# PwrGenBrd_v4_2.net
KiCad netlist of a schematic drawn in EAGLE
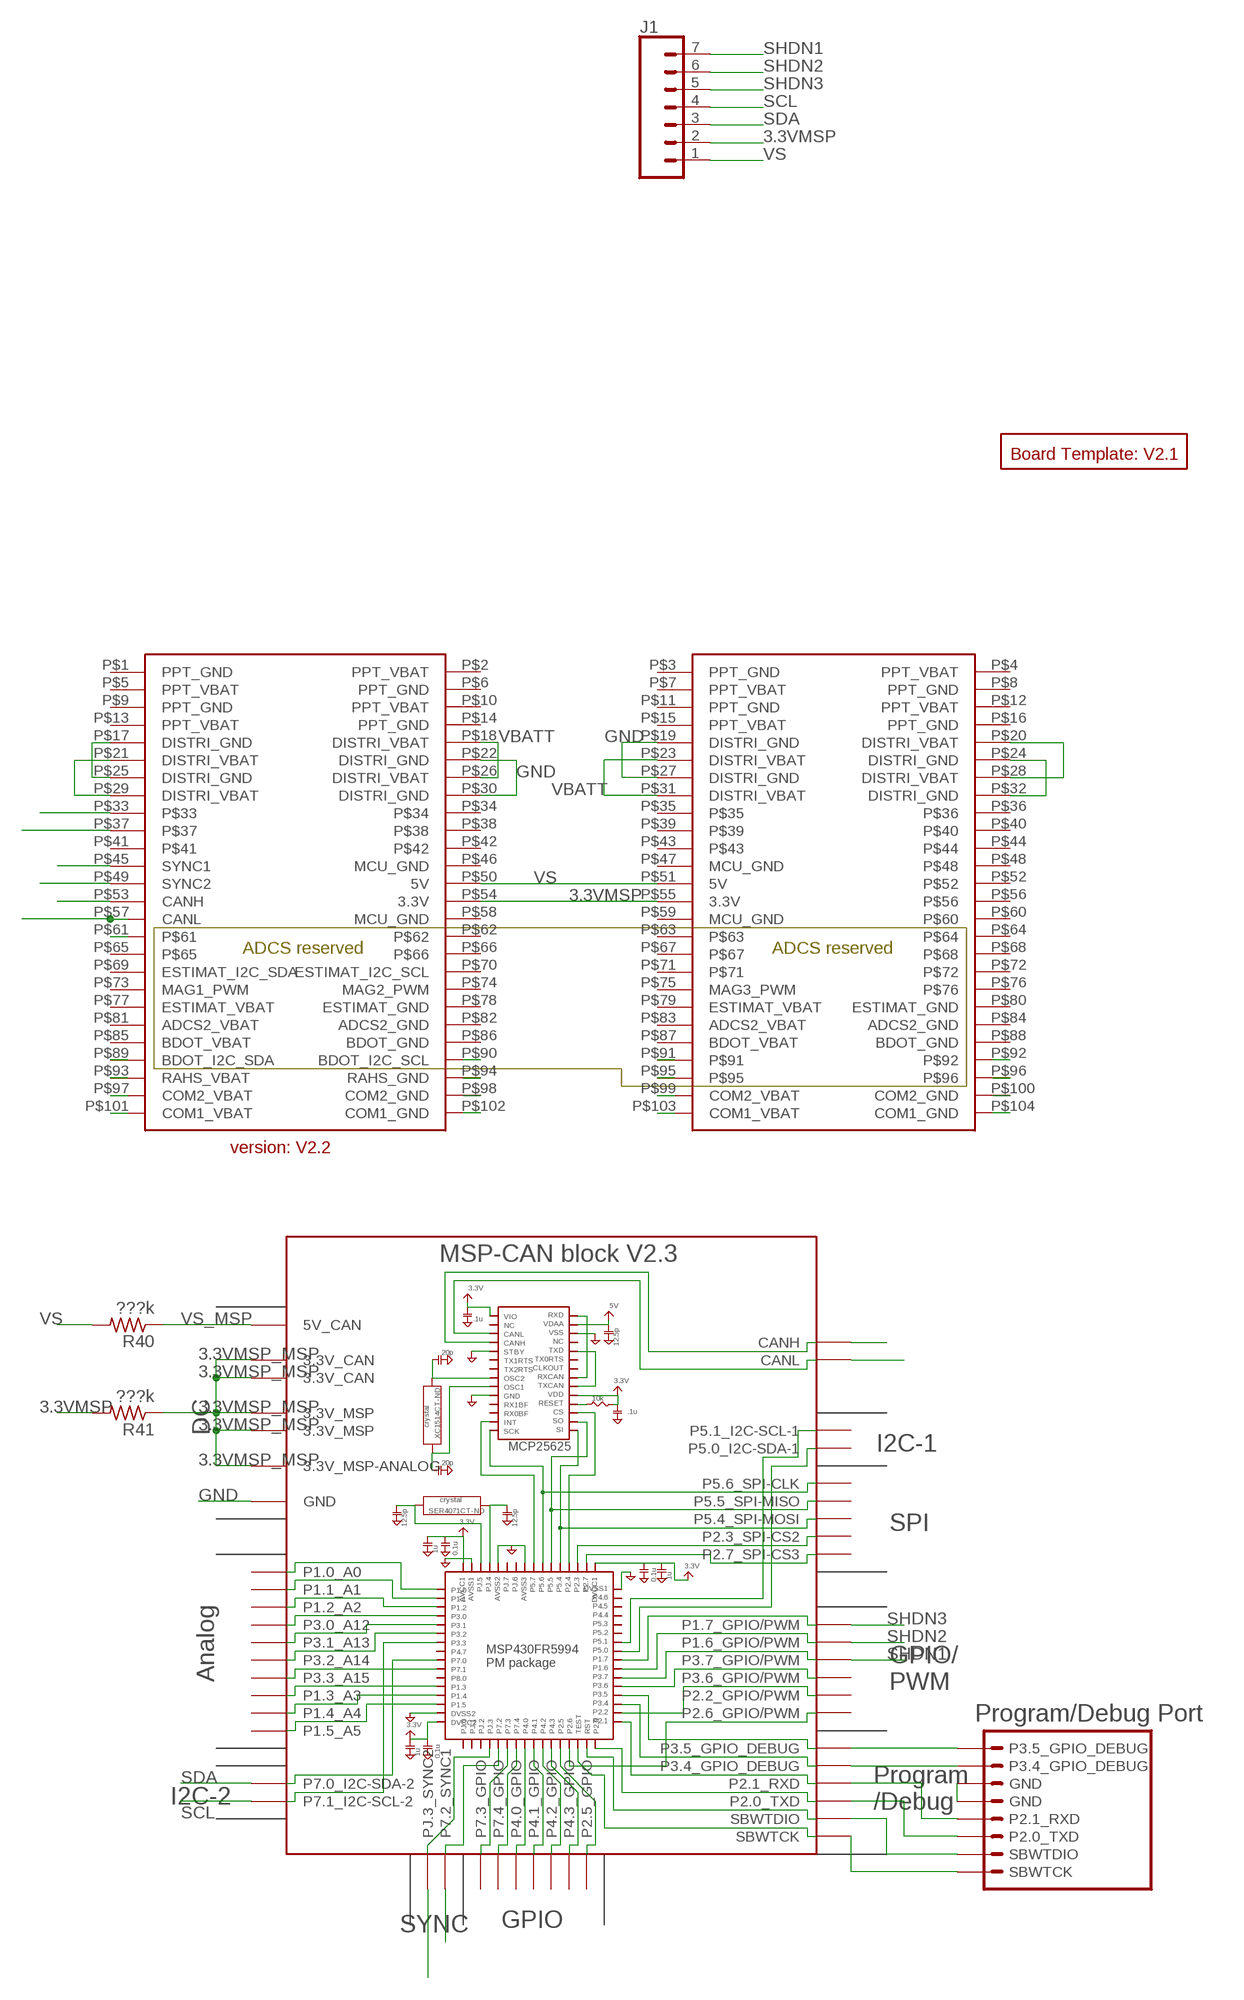
[diagram p0: schematic, sheet 1, part 1 of 2]
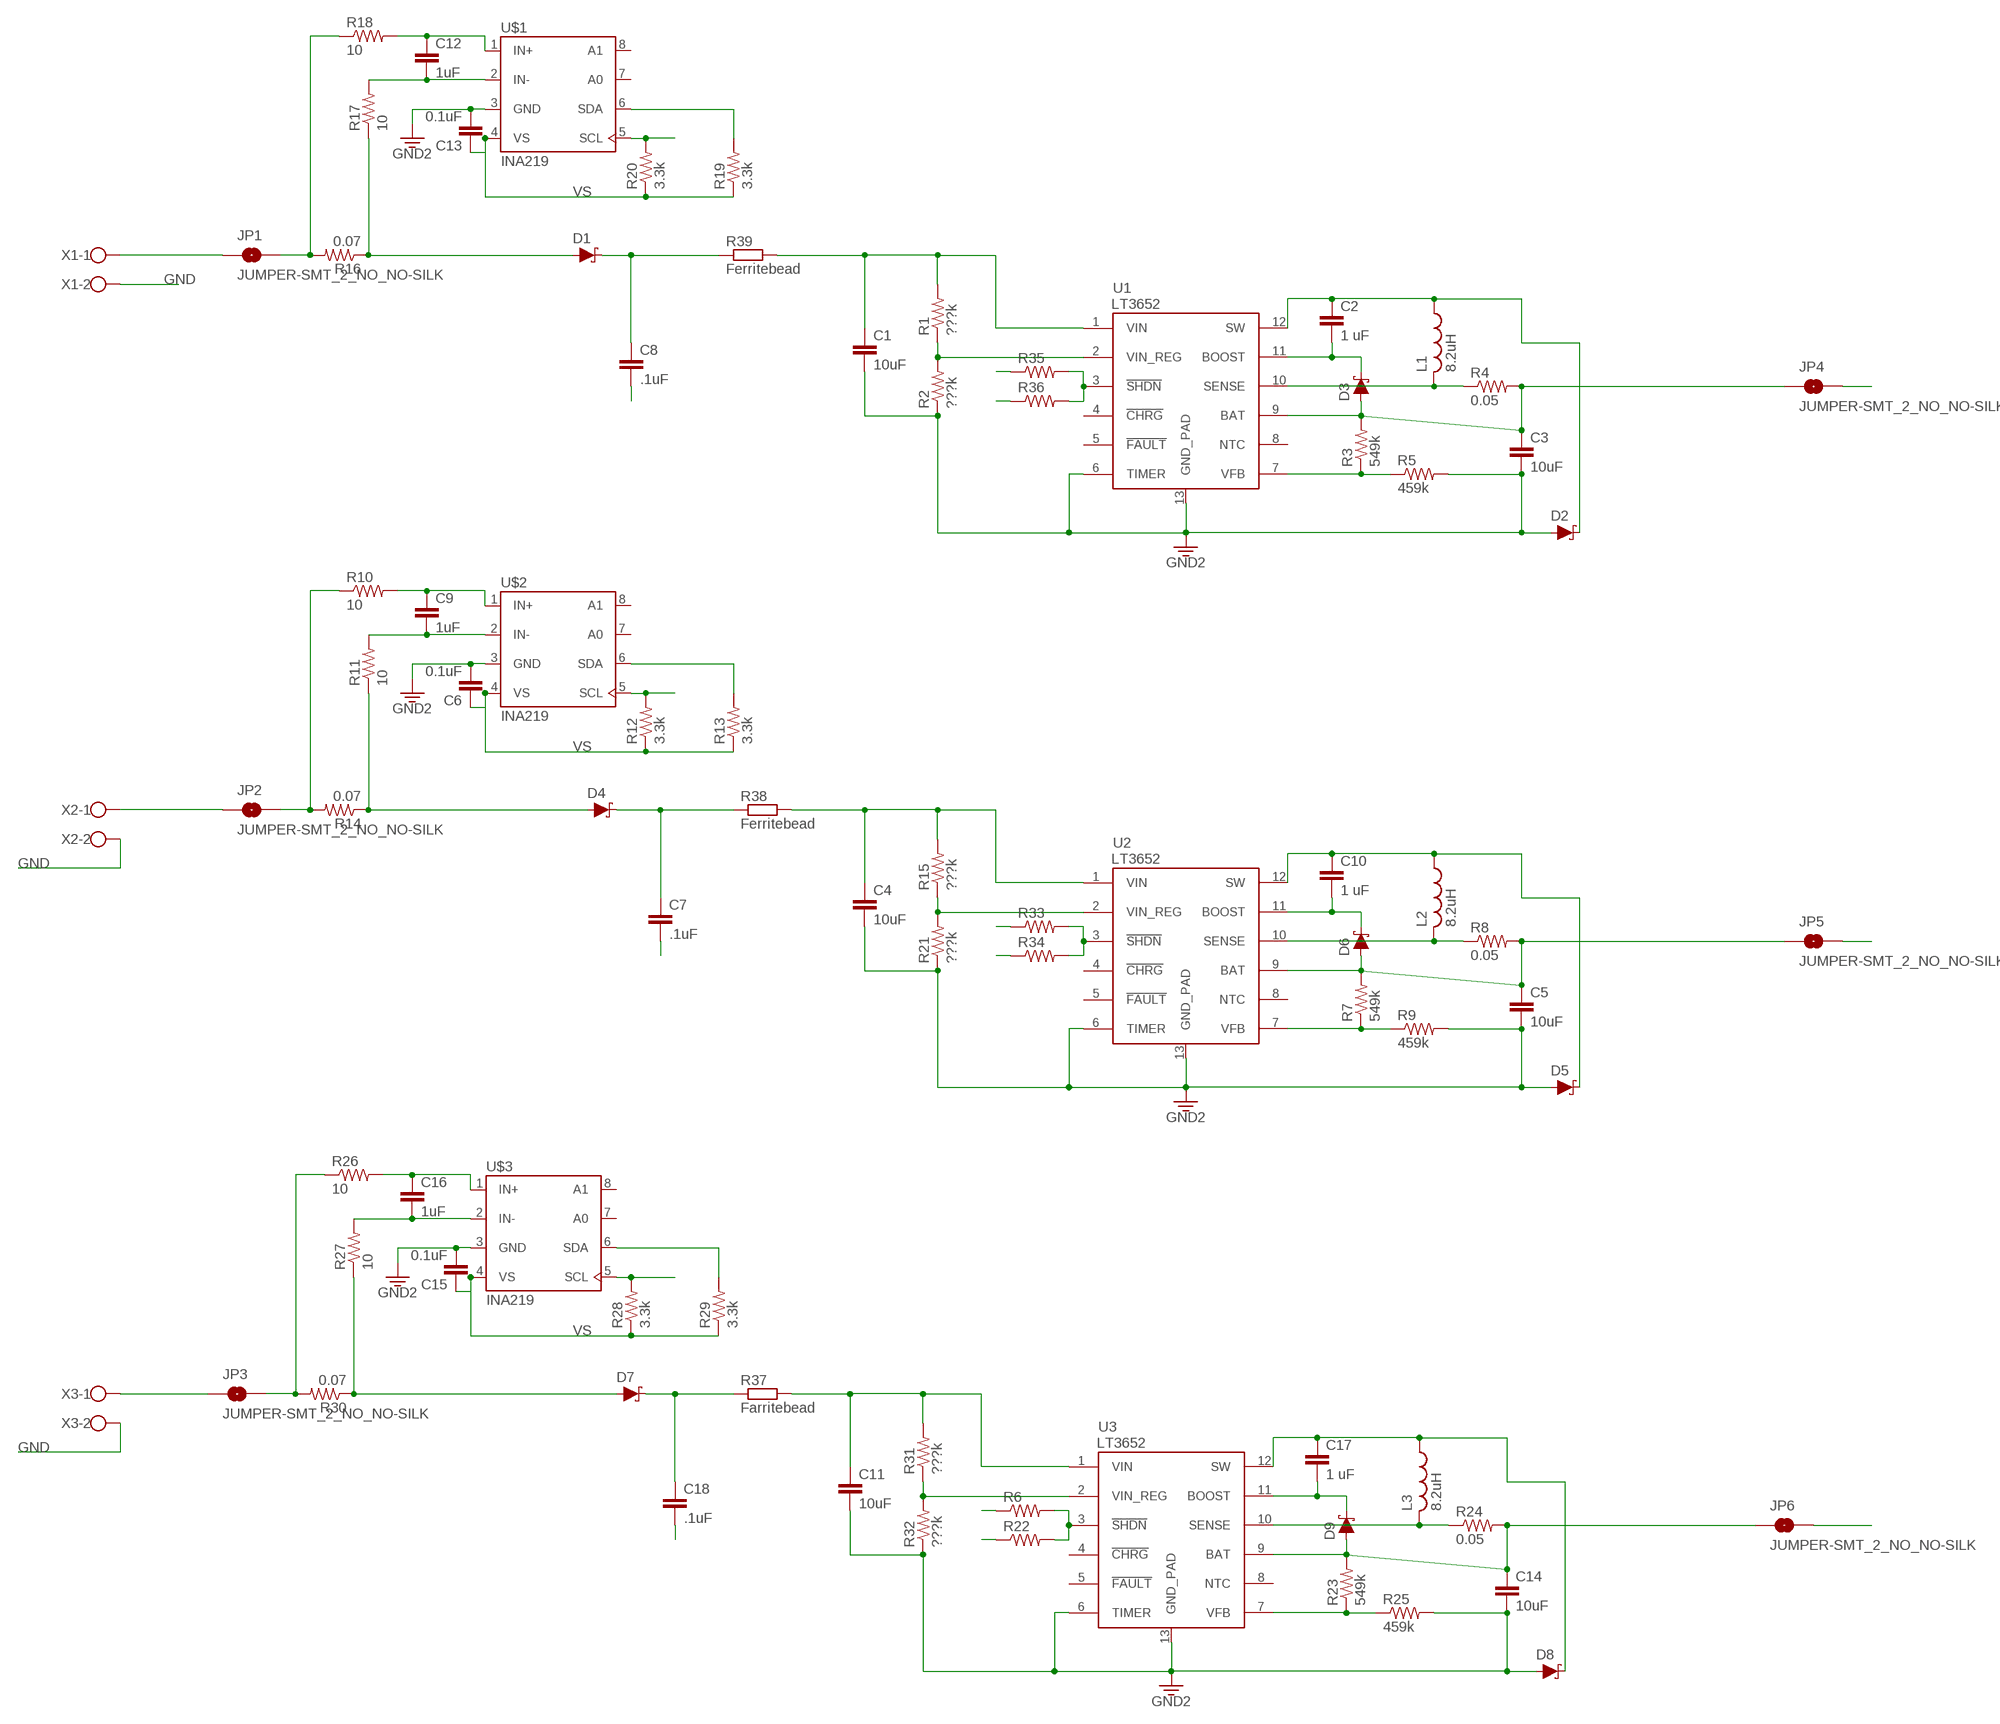
[diagram p1: schematic, sheet 1, part 2 of 2]

(export (version "E")
  (design (tool "Eeschema 10.0.6"))
  (components
    (comp (ref "C1")
      (value "10uF")
      (footprint "eagle-import:1210")
      (libsource (lib "eagle-import") (part "10UF-1210-50V-20%"))
    )
    (comp (ref "C2")
      (value "1 uF")
      (footprint "eagle-import:C0805")
      (libsource (lib "eagle-import") (part "C-EUC0805"))
    )
    (comp (ref "C3")
      (value "10uF")
      (footprint "eagle-import:C0805")
      (libsource (lib "eagle-import") (part "resistor_C-EUC0805"))
    )
    (comp (ref "C4")
      (value "10uF")
      (footprint "eagle-import:1210")
      (libsource (lib "eagle-import") (part "10UF-1210-50V-20%"))
    )
    (comp (ref "C5")
      (value "10uF")
      (footprint "eagle-import:C0805")
      (libsource (lib "eagle-import") (part "resistor_C-EUC0805"))
    )
    (comp (ref "C6")
      (value "0.1uF")
      (footprint "eagle-import:C0805")
      (libsource (lib "eagle-import") (part "resistor_C-EUC0805"))
    )
    (comp (ref "C7")
      (value ".1uF")
      (footprint "eagle-import:C0805")
      (libsource (lib "eagle-import") (part "C-EUC0805"))
    )
    (comp (ref "C8")
      (value ".1uF")
      (footprint "eagle-import:C0805")
      (libsource (lib "eagle-import") (part "C-EUC0805"))
    )
    (comp (ref "C9")
      (value "1uF")
      (footprint "eagle-import:C0805")
      (libsource (lib "eagle-import") (part "resistor_C-EUC0805"))
    )
    (comp (ref "C10")
      (value "1 uF")
      (footprint "eagle-import:C0805")
      (libsource (lib "eagle-import") (part "C-EUC0805"))
    )
    (comp (ref "C11")
      (value "10uF")
      (footprint "eagle-import:1210")
      (libsource (lib "eagle-import") (part "10UF-1210-50V-20%"))
    )
    (comp (ref "C12")
      (value "1uF")
      (footprint "eagle-import:C0805")
      (libsource (lib "eagle-import") (part "resistor_C-EUC0805"))
    )
    (comp (ref "C13")
      (value "0.1uF")
      (footprint "eagle-import:C0805")
      (libsource (lib "eagle-import") (part "resistor_C-EUC0805"))
    )
    (comp (ref "C14")
      (value "10uF")
      (footprint "eagle-import:C0805")
      (libsource (lib "eagle-import") (part "resistor_C-EUC0805"))
    )
    (comp (ref "C15")
      (value "0.1uF")
      (footprint "eagle-import:C0805")
      (libsource (lib "eagle-import") (part "resistor_C-EUC0805"))
    )
    (comp (ref "C16")
      (value "1uF")
      (footprint "eagle-import:C0805")
      (libsource (lib "eagle-import") (part "resistor_C-EUC0805"))
    )
    (comp (ref "C17")
      (value "1 uF")
      (footprint "eagle-import:C0805")
      (libsource (lib "eagle-import") (part "C-EUC0805"))
    )
    (comp (ref "C18")
      (value ".1uF")
      (footprint "eagle-import:C0805")
      (libsource (lib "eagle-import") (part "C-EUC0805"))
    )
    (comp (ref "D1")
      (value "DIODE-SCHOTTKY-B340A")
      (footprint "eagle-import:SMA-DIODE")
      (libsource (lib "eagle-import") (part "DIODE-SCHOTTKY-B340A"))
    )
    (comp (ref "D2")
      (value "DIODE-SCHOTTKY-B340A")
      (footprint "eagle-import:SMA-DIODE")
      (libsource (lib "eagle-import") (part "DIODE-SCHOTTKY-B340A"))
    )
    (comp (ref "D3")
      (value "DIODE-SCHOTTKY-ZLLS500")
      (footprint "eagle-import:SOT23-3")
      (libsource (lib "eagle-import") (part "DIODE-SCHOTTKY-ZLLS500"))
    )
    (comp (ref "D4")
      (value "DIODE-SCHOTTKY-B340A")
      (footprint "eagle-import:SMA-DIODE")
      (libsource (lib "eagle-import") (part "DIODE-SCHOTTKY-B340A"))
    )
    (comp (ref "D5")
      (value "DIODE-SCHOTTKY-B340A")
      (footprint "eagle-import:SMA-DIODE")
      (libsource (lib "eagle-import") (part "DIODE-SCHOTTKY-B340A"))
    )
    (comp (ref "D6")
      (value "DIODE-SCHOTTKY-ZLLS500")
      (footprint "eagle-import:SOT23-3")
      (libsource (lib "eagle-import") (part "DIODE-SCHOTTKY-ZLLS500"))
    )
    (comp (ref "D7")
      (value "DIODE-SCHOTTKY-B340A")
      (footprint "eagle-import:SMA-DIODE")
      (libsource (lib "eagle-import") (part "DIODE-SCHOTTKY-B340A"))
    )
    (comp (ref "D8")
      (value "DIODE-SCHOTTKY-B340A")
      (footprint "eagle-import:SMA-DIODE")
      (libsource (lib "eagle-import") (part "DIODE-SCHOTTKY-B340A"))
    )
    (comp (ref "D9")
      (value "DIODE-SCHOTTKY-ZLLS500")
      (footprint "eagle-import:SOT23-3")
      (libsource (lib "eagle-import") (part "DIODE-SCHOTTKY-ZLLS500"))
    )
    (comp (ref "J1")
      (value "CONN_07LOCK_LONGPADS")
      (footprint "eagle-import:1X07_LOCK_LONGPADS")
      (libsource (lib "eagle-import") (part "CONN_07LOCK_LONGPADS"))
    )
    (comp (ref "JP1")
      (value "JUMPER-SMT_2_NO_NO-SILK")
      (footprint "eagle-import:SMT-JUMPER_2_NO_NO-SILK")
      (libsource (lib "eagle-import") (part "JUMPER-SMT_2_NO_NO-SILK"))
    )
    (comp (ref "JP2")
      (value "JUMPER-SMT_2_NO_NO-SILK")
      (footprint "eagle-import:SMT-JUMPER_2_NO_NO-SILK")
      (libsource (lib "eagle-import") (part "JUMPER-SMT_2_NO_NO-SILK"))
    )
    (comp (ref "JP3")
      (value "JUMPER-SMT_2_NO_NO-SILK")
      (footprint "eagle-import:SMT-JUMPER_2_NO_NO-SILK")
      (libsource (lib "eagle-import") (part "JUMPER-SMT_2_NO_NO-SILK"))
    )
    (comp (ref "JP4")
      (value "JUMPER-SMT_2_NO_NO-SILK")
      (footprint "eagle-import:SMT-JUMPER_2_NO_NO-SILK")
      (libsource (lib "eagle-import") (part "JUMPER-SMT_2_NO_NO-SILK"))
    )
    (comp (ref "JP5")
      (value "JUMPER-SMT_2_NO_NO-SILK")
      (footprint "eagle-import:SMT-JUMPER_2_NO_NO-SILK")
      (libsource (lib "eagle-import") (part "JUMPER-SMT_2_NO_NO-SILK"))
    )
    (comp (ref "JP6")
      (value "JUMPER-SMT_2_NO_NO-SILK")
      (footprint "eagle-import:SMT-JUMPER_2_NO_NO-SILK")
      (libsource (lib "eagle-import") (part "JUMPER-SMT_2_NO_NO-SILK"))
    )
    (comp (ref "L1")
      (value "8.2uH")
      (footprint "eagle-import:L1812")
      (libsource (lib "eagle-import") (part "L-USL1812"))
    )
    (comp (ref "L2")
      (value "8.2uH")
      (footprint "eagle-import:L1812")
      (libsource (lib "eagle-import") (part "L-USL1812"))
    )
    (comp (ref "L3")
      (value "8.2uH")
      (footprint "eagle-import:L1812")
      (libsource (lib "eagle-import") (part "L-USL1812"))
    )
    (comp (ref "R1")
      (value "???k")
      (footprint "eagle-import:R0805")
      (libsource (lib "eagle-import") (part "R-US_R0805"))
    )
    (comp (ref "R2")
      (value "???k")
      (footprint "eagle-import:R0805")
      (libsource (lib "eagle-import") (part "R-US_R0805"))
    )
    (comp (ref "R3")
      (value "549k")
      (footprint "eagle-import:R0805")
      (libsource (lib "eagle-import") (part "R-US_R0805"))
    )
    (comp (ref "R4")
      (value "0.05")
      (footprint "eagle-import:R0805")
      (libsource (lib "eagle-import") (part "R-US_R0805"))
    )
    (comp (ref "R5")
      (value "459k")
      (footprint "eagle-import:R0805")
      (libsource (lib "eagle-import") (part "R-US_R0805"))
    )
    (comp (ref "R6")
      (value "R-US_R0805")
      (footprint "eagle-import:R0805")
      (libsource (lib "eagle-import") (part "R-US_R0805"))
    )
    (comp (ref "R7")
      (value "549k")
      (footprint "eagle-import:R0805")
      (libsource (lib "eagle-import") (part "R-US_R0805"))
    )
    (comp (ref "R8")
      (value "0.05")
      (footprint "eagle-import:R0805")
      (libsource (lib "eagle-import") (part "R-US_R0805"))
    )
    (comp (ref "R9")
      (value "459k")
      (footprint "eagle-import:R0805")
      (libsource (lib "eagle-import") (part "R-US_R0805"))
    )
    (comp (ref "R10")
      (value "10")
      (footprint "eagle-import:R0805")
      (libsource (lib "eagle-import") (part "R-US_R0805"))
    )
    (comp (ref "R11")
      (value "10")
      (footprint "eagle-import:R0805")
      (libsource (lib "eagle-import") (part "R-US_R0805"))
    )
    (comp (ref "R12")
      (value "3.3k")
      (footprint "eagle-import:R0805")
      (libsource (lib "eagle-import") (part "R-US_R0805"))
    )
    (comp (ref "R13")
      (value "3.3k")
      (footprint "eagle-import:R0805")
      (libsource (lib "eagle-import") (part "R-US_R0805"))
    )
    (comp (ref "R14")
      (value "0.07")
      (footprint "eagle-import:R0805")
      (libsource (lib "eagle-import") (part "R-US_R0805"))
    )
    (comp (ref "R15")
      (value "???k")
      (footprint "eagle-import:R0805")
      (libsource (lib "eagle-import") (part "R-US_R0805"))
    )
    (comp (ref "R16")
      (value "0.07")
      (footprint "eagle-import:R0805")
      (libsource (lib "eagle-import") (part "R-US_R0805"))
    )
    (comp (ref "R17")
      (value "10")
      (footprint "eagle-import:R0805")
      (libsource (lib "eagle-import") (part "R-US_R0805"))
    )
    (comp (ref "R18")
      (value "10")
      (footprint "eagle-import:R0805")
      (libsource (lib "eagle-import") (part "R-US_R0805"))
    )
    (comp (ref "R19")
      (value "3.3k")
      (footprint "eagle-import:R0805")
      (libsource (lib "eagle-import") (part "R-US_R0805"))
    )
    (comp (ref "R20")
      (value "3.3k")
      (footprint "eagle-import:R0805")
      (libsource (lib "eagle-import") (part "R-US_R0805"))
    )
    (comp (ref "R21")
      (value "???k")
      (footprint "eagle-import:R0805")
      (libsource (lib "eagle-import") (part "R-US_R0805"))
    )
    (comp (ref "R22")
      (value "R-US_R0805")
      (footprint "eagle-import:R0805")
      (libsource (lib "eagle-import") (part "R-US_R0805"))
    )
    (comp (ref "R23")
      (value "549k")
      (footprint "eagle-import:R0805")
      (libsource (lib "eagle-import") (part "R-US_R0805"))
    )
    (comp (ref "R24")
      (value "0.05")
      (footprint "eagle-import:R0805")
      (libsource (lib "eagle-import") (part "R-US_R0805"))
    )
    (comp (ref "R25")
      (value "459k")
      (footprint "eagle-import:R0805")
      (libsource (lib "eagle-import") (part "R-US_R0805"))
    )
    (comp (ref "R26")
      (value "10")
      (footprint "eagle-import:R0805")
      (libsource (lib "eagle-import") (part "R-US_R0805"))
    )
    (comp (ref "R27")
      (value "10")
      (footprint "eagle-import:R0805")
      (libsource (lib "eagle-import") (part "R-US_R0805"))
    )
    (comp (ref "R28")
      (value "3.3k")
      (footprint "eagle-import:R0805")
      (libsource (lib "eagle-import") (part "R-US_R0805"))
    )
    (comp (ref "R29")
      (value "3.3k")
      (footprint "eagle-import:R0805")
      (libsource (lib "eagle-import") (part "R-US_R0805"))
    )
    (comp (ref "R30")
      (value "0.07")
      (footprint "eagle-import:R0805")
      (libsource (lib "eagle-import") (part "R-US_R0805"))
    )
    (comp (ref "R31")
      (value "???k")
      (footprint "eagle-import:R0805")
      (libsource (lib "eagle-import") (part "R-US_R0805"))
    )
    (comp (ref "R32")
      (value "???k")
      (footprint "eagle-import:R0805")
      (libsource (lib "eagle-import") (part "R-US_R0805"))
    )
    (comp (ref "R33")
      (value "R-US_R0805")
      (footprint "eagle-import:R0805")
      (libsource (lib "eagle-import") (part "R-US_R0805"))
    )
    (comp (ref "R34")
      (value "R-US_R0805")
      (footprint "eagle-import:R0805")
      (libsource (lib "eagle-import") (part "R-US_R0805"))
    )
    (comp (ref "R35")
      (value "R-US_R0805")
      (footprint "eagle-import:R0805")
      (libsource (lib "eagle-import") (part "R-US_R0805"))
    )
    (comp (ref "R36")
      (value "R-US_R0805")
      (footprint "eagle-import:R0805")
      (libsource (lib "eagle-import") (part "R-US_R0805"))
    )
    (comp (ref "R37")
      (value "Farritebead")
      (footprint "eagle-import:R1206")
      (libsource (lib "eagle-import") (part "R-EU_R1206"))
    )
    (comp (ref "R38")
      (value "Ferritebead")
      (footprint "eagle-import:R1206")
      (libsource (lib "eagle-import") (part "R-EU_R1206"))
    )
    (comp (ref "R39")
      (value "Ferritebead")
      (footprint "eagle-import:R1206")
      (libsource (lib "eagle-import") (part "R-EU_R1206"))
    )
    (comp (ref "R40")
      (value "???k")
      (footprint "eagle-import:R0805")
      (libsource (lib "eagle-import") (part "R-US_R0805"))
    )
    (comp (ref "R41")
      (value "???k")
      (footprint "eagle-import:R0805")
      (libsource (lib "eagle-import") (part "R-US_R0805"))
    )
    (comp (ref "U$1")
      (value "INA219")
      (footprint "eagle-import:SO08")
      (libsource (lib "eagle-import") (part "INA219"))
    )
    (comp (ref "U$2")
      (value "INA219")
      (footprint "eagle-import:SO08")
      (libsource (lib "eagle-import") (part "INA219"))
    )
    (comp (ref "U$3")
      (value "INA219")
      (footprint "eagle-import:SO08")
      (libsource (lib "eagle-import") (part "INA219"))
    )
    (comp (ref "U$4")
      (value "PC104_CONNECTOR")
      (footprint "eagle-import:PC104_CONNECTOR")
      (libsource (lib "eagle-import") (part "PC104_CONNECTOR"))
    )
    (comp (ref "U$5")
      (value "MSP-CAN_BLOCK")
      (footprint "eagle-import:MSP-CAN_BLOCK")
      (libsource (lib "eagle-import") (part "MSP-CAN_BLOCK"))
    )
    (comp (ref "U$6")
      (value "BOARD_TEMPLATE_(V2.1)")
      (footprint "eagle-import:BOARD_TEMPLATE_(V2.1)")
      (libsource (lib "eagle-import") (part "BOARD_TEMPLATE_(V2.1)"))
    )
    (comp (ref "U$8")
      (value "PROGRAM/DEBUG_PORT")
      (footprint "eagle-import:1X08_CONNECTOR")
      (libsource (lib "eagle-import") (part "PROGRAM/DEBUG_PORT"))
    )
    (comp (ref "U1")
      (value "LT3652")
      (footprint "eagle-import:MSOP-12_GND")
      (libsource (lib "eagle-import") (part "LT3652"))
    )
    (comp (ref "U2")
      (value "LT3652")
      (footprint "eagle-import:MSOP-12_GND")
      (libsource (lib "eagle-import") (part "LT3652"))
    )
    (comp (ref "U3")
      (value "LT3652")
      (footprint "eagle-import:MSOP-12_GND")
      (libsource (lib "eagle-import") (part "LT3652"))
    )
    (comp (ref "X1")
      (value "W237-102")
      (footprint "eagle-import:W237-102")
      (fields (field (name "MPN") "237-102"))
      (libsource (lib "eagle-import") (part "W237-102"))
    )
    (comp (ref "X2")
      (value "W237-102")
      (footprint "eagle-import:W237-102")
      (fields (field (name "MPN") "237-102"))
      (libsource (lib "eagle-import") (part "W237-102"))
    )
    (comp (ref "X3")
      (value "W237-102")
      (footprint "eagle-import:W237-102")
      (fields (field (name "MPN") "237-102"))
      (libsource (lib "eagle-import") (part "W237-102"))
    )
  )
  (nets
    (net (code "1") (name "3.3VMSP") (class "Default")
      (node (ref "J1") (pin "2") (pinfunction "2_2") (pintype "passive"))
      (node (ref "R41") (pin "2") (pinfunction "2_2") (pintype "passive"))
      (node (ref "U$4") (pin "P$54") (pinfunction "3.3V_P$54") (pintype "bidirectional"))
      (node (ref "U$4") (pin "P$55") (pinfunction "3.3V_P$55") (pintype "bidirectional"))
    )
    (net (code "2") (name "3.3VMSP_MSP") (class "Default")
      (node (ref "R41") (pin "1") (pinfunction "1_1") (pintype "passive"))
      (node (ref "U$5") (pin "3.3V@CAN1") (pinfunction "3.3V_CAN_3.3V@CAN1") (pintype "bidirectional"))
      (node (ref "U$5") (pin "3.3V@CAN2") (pinfunction "3.3V_CAN_3.3V@CAN2") (pintype "bidirectional"))
      (node (ref "U$5") (pin "3.3V@MSP1") (pinfunction "3.3V_MSP_3.3V@MSP1") (pintype "bidirectional"))
      (node (ref "U$5") (pin "3.3V@MSP2") (pinfunction "3.3V_MSP_3.3V@MSP2") (pintype "bidirectional"))
      (node (ref "U$5") (pin "3.3V_ANALOG@MSP2") (pinfunction "3.3V_MSP-ANALOG_3.3V_ANALOG@MSP2") (pintype "bidirectional"))
    )
    (net (code "3") (name "CANH") (class "Default")
      (node (ref "U$4") (pin "P$53") (pinfunction "CANH_P$53") (pintype "bidirectional"))
      (node (ref "U$5") (pin "CANH") (pinfunction "CANH_CANH") (pintype "bidirectional"))
    )
    (net (code "4") (name "CANL") (class "Default")
      (node (ref "U$4") (pin "P$57") (pinfunction "CANL_P$57") (pintype "bidirectional"))
      (node (ref "U$5") (pin "CANL") (pinfunction "CANL_CANL") (pintype "bidirectional"))
    )
    (net (code "5") (name "GND") (class "Default")
      (node (ref "C1") (pin "2") (pinfunction "2_2") (pintype "passive"))
      (node (ref "C11") (pin "2") (pinfunction "2_2") (pintype "passive"))
      (node (ref "C13") (pin "2") (pinfunction "2_2") (pintype "passive"))
      (node (ref "C14") (pin "2") (pinfunction "2_2") (pintype "passive"))
      (node (ref "C15") (pin "2") (pinfunction "2_2") (pintype "passive"))
      (node (ref "C18") (pin "2") (pinfunction "2_2") (pintype "passive"))
      (node (ref "C3") (pin "2") (pinfunction "2_2") (pintype "passive"))
      (node (ref "C4") (pin "2") (pinfunction "2_2") (pintype "passive"))
      (node (ref "C5") (pin "2") (pinfunction "2_2") (pintype "passive"))
      (node (ref "C6") (pin "2") (pinfunction "2_2") (pintype "passive"))
      (node (ref "C7") (pin "2") (pinfunction "2_2") (pintype "passive"))
      (node (ref "C8") (pin "2") (pinfunction "2_2") (pintype "passive"))
      (node (ref "D2") (pin "A") (pinfunction "A_A") (pintype "passive"))
      (node (ref "D5") (pin "A") (pinfunction "A_A") (pintype "passive"))
      (node (ref "D8") (pin "A") (pinfunction "A_A") (pintype "passive"))
      (node (ref "R2") (pin "1") (pinfunction "1_1") (pintype "passive"))
      (node (ref "R21") (pin "1") (pinfunction "1_1") (pintype "passive"))
      (node (ref "R25") (pin "2") (pinfunction "2_2") (pintype "passive"))
      (node (ref "R32") (pin "1") (pinfunction "1_1") (pintype "passive"))
      (node (ref "R5") (pin "2") (pinfunction "2_2") (pintype "passive"))
      (node (ref "R9") (pin "2") (pinfunction "2_2") (pintype "passive"))
      (node (ref "U$1") (pin "3") (pinfunction "GND_3") (pintype "power_in"))
      (node (ref "U$2") (pin "3") (pinfunction "GND_3") (pintype "power_in"))
      (node (ref "U$3") (pin "3") (pinfunction "GND_3") (pintype "power_in"))
      (node (ref "U$4") (pin "P$17") (pinfunction "DISTRI_GND_P$17") (pintype "bidirectional"))
      (node (ref "U$4") (pin "P$19") (pinfunction "DISTRI_GND_P$19") (pintype "bidirectional"))
      (node (ref "U$4") (pin "P$22") (pinfunction "DISTRI_GND_P$22") (pintype "bidirectional"))
      (node (ref "U$4") (pin "P$24") (pinfunction "DISTRI_GND_P$24") (pintype "bidirectional"))
      (node (ref "U$4") (pin "P$25") (pinfunction "DISTRI_GND_P$25") (pintype "bidirectional"))
      (node (ref "U$4") (pin "P$27") (pinfunction "DISTRI_GND_P$27") (pintype "bidirectional"))
      (node (ref "U$4") (pin "P$30") (pinfunction "DISTRI_GND_P$30") (pintype "bidirectional"))
      (node (ref "U$4") (pin "P$32") (pinfunction "DISTRI_GND_P$32") (pintype "bidirectional"))
      (node (ref "U$5") (pin "GND@1") (pinfunction "GND_GND@1") (pintype "bidirectional"))
      (node (ref "U$5") (pin "GND@10") (pinfunction "GND_GND@10") (pintype "bidirectional"))
      (node (ref "U$5") (pin "GND@11") (pinfunction "GND_GND@11") (pintype "bidirectional"))
      (node (ref "U$5") (pin "GND@12") (pinfunction "GND_GND@12") (pintype "bidirectional"))
      (node (ref "U$5") (pin "GND@13") (pinfunction "GND_GND@13") (pintype "bidirectional"))
      (node (ref "U$5") (pin "GND@14") (pinfunction "GND_GND@14") (pintype "bidirectional"))
      (node (ref "U$5") (pin "GND@15") (pinfunction "GND_GND@15") (pintype "bidirectional"))
      (node (ref "U$5") (pin "GND@16") (pinfunction "GND_GND@16") (pintype "bidirectional"))
      (node (ref "U$5") (pin "GND@17") (pinfunction "GND_GND@17") (pintype "bidirectional"))
      (node (ref "U$5") (pin "GND@2") (pinfunction "GND_GND@2") (pintype "bidirectional"))
      (node (ref "U$5") (pin "GND@26") (pinfunction "GND_GND@26") (pintype "bidirectional"))
      (node (ref "U$5") (pin "GND@3") (pinfunction "GND_GND@3") (pintype "bidirectional"))
      (node (ref "U$5") (pin "GND@4") (pinfunction "GND_GND@4") (pintype "bidirectional"))
      (node (ref "U$5") (pin "GND@5") (pinfunction "GND_GND@5") (pintype "bidirectional"))
      (node (ref "U$5") (pin "GND@7") (pinfunction "GND_GND@7") (pintype "bidirectional"))
      (node (ref "U$5") (pin "GND@8") (pinfunction "GND_GND@8") (pintype "bidirectional"))
      (node (ref "U$5") (pin "GND@9") (pinfunction "GND_GND@9") (pintype "bidirectional"))
      (node (ref "U$8") (pin "5") (pinfunction "GND_5") (pintype "bidirectional"))
      (node (ref "U$8") (pin "6") (pinfunction "GND_6") (pintype "bidirectional"))
      (node (ref "U1") (pin "13") (pinfunction "GND_PAD_13") (pintype "bidirectional"))
      (node (ref "U1") (pin "6") (pinfunction "TIMER_6") (pintype "bidirectional"))
      (node (ref "U2") (pin "13") (pinfunction "GND_PAD_13") (pintype "bidirectional"))
      (node (ref "U2") (pin "6") (pinfunction "TIMER_6") (pintype "bidirectional"))
      (node (ref "U3") (pin "13") (pinfunction "GND_PAD_13") (pintype "bidirectional"))
      (node (ref "U3") (pin "6") (pinfunction "TIMER_6") (pintype "bidirectional"))
      (node (ref "X1") (pin "2") (pinfunction "KL_2") (pintype "passive"))
      (node (ref "X2") (pin "2") (pinfunction "KL_2") (pintype "passive"))
      (node (ref "X3") (pin "2") (pinfunction "KL_2") (pintype "passive"))
    )
    (net (code "6") (name "Net-(C7-Pad1)") (class "Default")
      (node (ref "C7") (pin "1") (pinfunction "1_1") (pintype "passive"))
      (node (ref "D4") (pin "C") (pinfunction "C_C") (pintype "passive"))
      (node (ref "R38") (pin "1") (pinfunction "1_1") (pintype "passive"))
    )
    (net (code "7") (name "Net-(C8-Pad1)") (class "Default")
      (node (ref "C8") (pin "1") (pinfunction "1_1") (pintype "passive"))
      (node (ref "D1") (pin "C") (pinfunction "C_C") (pintype "passive"))
      (node (ref "R39") (pin "1") (pinfunction "1_1") (pintype "passive"))
    )
    (net (code "8") (name "Net-(C18-Pad1)") (class "Default")
      (node (ref "C18") (pin "1") (pinfunction "1_1") (pintype "passive"))
      (node (ref "D7") (pin "C") (pinfunction "C_C") (pintype "passive"))
      (node (ref "R37") (pin "1") (pinfunction "1_1") (pintype "passive"))
    )
    (net (code "9") (name "Net-(D1-PadA)") (class "Default")
      (node (ref "D1") (pin "A") (pinfunction "A_A") (pintype "passive"))
      (node (ref "R16") (pin "1") (pinfunction "1_1") (pintype "passive"))
      (node (ref "R17") (pin "1") (pinfunction "1_1") (pintype "passive"))
    )
    (net (code "10") (name "Net-(D3-A)") (class "Default")
      (node (ref "C3") (pin "1") (pinfunction "1_1") (pintype "passive"))
      (node (ref "D3") (pin "1") (pinfunction "A_1") (pintype "passive"))
      (node (ref "JP4") (pin "1") (pinfunction "1_1") (pintype "passive"))
      (node (ref "R3") (pin "2") (pinfunction "2_2") (pintype "passive"))
      (node (ref "R4") (pin "2") (pinfunction "2_2") (pintype "passive"))
      (node (ref "U1") (pin "9") (pinfunction "BAT_9") (pintype "bidirectional"))
    )
    (net (code "11") (name "Net-(D3-C)") (class "Default")
      (node (ref "C2") (pin "2") (pinfunction "2_2") (pintype "passive"))
      (node (ref "D3") (pin "3") (pinfunction "C_3") (pintype "passive"))
      (node (ref "U1") (pin "11") (pinfunction "BOOST_11") (pintype "bidirectional"))
    )
    (net (code "12") (name "Net-(D4-PadA)") (class "Default")
      (node (ref "D4") (pin "A") (pinfunction "A_A") (pintype "passive"))
      (node (ref "R11") (pin "1") (pinfunction "1_1") (pintype "passive"))
      (node (ref "R14") (pin "1") (pinfunction "1_1") (pintype "passive"))
    )
    (net (code "13") (name "Net-(D6-A)") (class "Default")
      (node (ref "C5") (pin "1") (pinfunction "1_1") (pintype "passive"))
      (node (ref "D6") (pin "1") (pinfunction "A_1") (pintype "passive"))
      (node (ref "JP5") (pin "1") (pinfunction "1_1") (pintype "passive"))
      (node (ref "R7") (pin "2") (pinfunction "2_2") (pintype "passive"))
      (node (ref "R8") (pin "2") (pinfunction "2_2") (pintype "passive"))
      (node (ref "U2") (pin "9") (pinfunction "BAT_9") (pintype "bidirectional"))
    )
    (net (code "14") (name "Net-(D6-C)") (class "Default")
      (node (ref "C10") (pin "2") (pinfunction "2_2") (pintype "passive"))
      (node (ref "D6") (pin "3") (pinfunction "C_3") (pintype "passive"))
      (node (ref "U2") (pin "11") (pinfunction "BOOST_11") (pintype "bidirectional"))
    )
    (net (code "15") (name "Net-(D7-PadA)") (class "Default")
      (node (ref "D7") (pin "A") (pinfunction "A_A") (pintype "passive"))
      (node (ref "R27") (pin "1") (pinfunction "1_1") (pintype "passive"))
      (node (ref "R30") (pin "1") (pinfunction "1_1") (pintype "passive"))
    )
    (net (code "16") (name "Net-(D9-A)") (class "Default")
      (node (ref "C14") (pin "1") (pinfunction "1_1") (pintype "passive"))
      (node (ref "D9") (pin "1") (pinfunction "A_1") (pintype "passive"))
      (node (ref "JP6") (pin "1") (pinfunction "1_1") (pintype "passive"))
      (node (ref "R23") (pin "2") (pinfunction "2_2") (pintype "passive"))
      (node (ref "R24") (pin "2") (pinfunction "2_2") (pintype "passive"))
      (node (ref "U3") (pin "9") (pinfunction "BAT_9") (pintype "bidirectional"))
    )
    (net (code "17") (name "Net-(D9-C)") (class "Default")
      (node (ref "C17") (pin "2") (pinfunction "2_2") (pintype "passive"))
      (node (ref "D9") (pin "3") (pinfunction "C_3") (pintype "passive"))
      (node (ref "U3") (pin "11") (pinfunction "BOOST_11") (pintype "bidirectional"))
    )
    (net (code "18") (name "Net-(JP1-Pad2)") (class "Default")
      (node (ref "JP1") (pin "2") (pinfunction "2_2") (pintype "passive"))
      (node (ref "R16") (pin "2") (pinfunction "2_2") (pintype "passive"))
      (node (ref "R18") (pin "1") (pinfunction "1_1") (pintype "passive"))
    )
    (net (code "19") (name "Net-(JP2-Pad2)") (class "Default")
      (node (ref "JP2") (pin "2") (pinfunction "2_2") (pintype "passive"))
      (node (ref "R10") (pin "1") (pinfunction "1_1") (pintype "passive"))
      (node (ref "R14") (pin "2") (pinfunction "2_2") (pintype "passive"))
    )
    (net (code "20") (name "Net-(JP3-Pad2)") (class "Default")
      (node (ref "JP3") (pin "2") (pinfunction "2_2") (pintype "passive"))
      (node (ref "R26") (pin "1") (pinfunction "1_1") (pintype "passive"))
      (node (ref "R30") (pin "2") (pinfunction "2_2") (pintype "passive"))
    )
    (net (code "21") (name "Net-(U$1-IN+)") (class "Default")
      (node (ref "C12") (pin "1") (pinfunction "1_1") (pintype "passive"))
      (node (ref "R18") (pin "2") (pinfunction "2_2") (pintype "passive"))
      (node (ref "U$1") (pin "1") (pinfunction "IN+_1") (pintype "input"))
    )
    (net (code "22") (name "Net-(U$1-IN-)") (class "Default")
      (node (ref "C12") (pin "2") (pinfunction "2_2") (pintype "passive"))
      (node (ref "R17") (pin "2") (pinfunction "2_2") (pintype "passive"))
      (node (ref "U$1") (pin "2") (pinfunction "IN-_2") (pintype "input"))
    )
    (net (code "23") (name "Net-(U$2-IN+)") (class "Default")
      (node (ref "C9") (pin "1") (pinfunction "1_1") (pintype "passive"))
      (node (ref "R10") (pin "2") (pinfunction "2_2") (pintype "passive"))
      (node (ref "U$2") (pin "1") (pinfunction "IN+_1") (pintype "input"))
    )
    (net (code "24") (name "Net-(U$2-IN-)") (class "Default")
      (node (ref "C9") (pin "2") (pinfunction "2_2") (pintype "passive"))
      (node (ref "R11") (pin "2") (pinfunction "2_2") (pintype "passive"))
      (node (ref "U$2") (pin "2") (pinfunction "IN-_2") (pintype "input"))
    )
    (net (code "25") (name "Net-(U$3-IN+)") (class "Default")
      (node (ref "C16") (pin "1") (pinfunction "1_1") (pintype "passive"))
      (node (ref "R26") (pin "2") (pinfunction "2_2") (pintype "passive"))
      (node (ref "U$3") (pin "1") (pinfunction "IN+_1") (pintype "input"))
    )
    (net (code "26") (name "Net-(U$3-IN-)") (class "Default")
      (node (ref "C16") (pin "2") (pinfunction "2_2") (pintype "passive"))
      (node (ref "R27") (pin "2") (pinfunction "2_2") (pintype "passive"))
      (node (ref "U$3") (pin "2") (pinfunction "IN-_2") (pintype "input"))
    )
    (net (code "27") (name "Net-(U$5-PadSBWTCK)") (class "Default")
      (node (ref "U$5") (pin "SBWTCK") (pinfunction "SBWTCK_SBWTCK") (pintype "bidirectional"))
      (node (ref "U$8") (pin "SBWTCK") (pinfunction "SBWTCK_SBWTCK") (pintype "bidirectional"))
    )
    (net (code "28") (name "Net-(U$8-P2.0_TXD)") (class "Default")
      (node (ref "U$5") (pin "P2.0_TXD") (pinfunction "P2.0_TXD_P2.0_TXD") (pintype "bidirectional"))
      (node (ref "U$8") (pin "3") (pinfunction "P2.0_TXD_3") (pintype "bidirectional"))
    )
    (net (code "29") (name "Net-(U$8-P2.1_RXD)") (class "Default")
      (node (ref "U$5") (pin "P2.1_RXD") (pinfunction "P2.1_RXD_P2.1_RXD") (pintype "bidirectional"))
      (node (ref "U$8") (pin "4") (pinfunction "P2.1_RXD_4") (pintype "bidirectional"))
    )
    (net (code "30") (name "Net-(U$8-P3.4_GPIO_DEBUG)") (class "Default")
      (node (ref "U$5") (pin "P3.4_GPIO_DEBUG") (pinfunction "P3.4_GPIO_DEBUG_P3.4_GPIO_DEBUG") (pintype "bidirectional"))
      (node (ref "U$8") (pin "7") (pinfunction "P3.4_GPIO_DEBUG_7") (pintype "bidirectional"))
    )
    (net (code "31") (name "Net-(U$8-P3.5_GPIO_DEBUG)") (class "Default")
      (node (ref "U$5") (pin "P3.5_GPIO_DEBUG") (pinfunction "P3.5_GPIO_DEBUG_P3.5_GPIO_DEBUG") (pintype "bidirectional"))
      (node (ref "U$8") (pin "8") (pinfunction "P3.5_GPIO_DEBUG_8") (pintype "bidirectional"))
    )
    (net (code "32") (name "Net-(U$8-SBWTDIO)") (class "Default")
      (node (ref "U$5") (pin "SBWTDIO") (pinfunction "SBWTDIO_SBWTDIO") (pintype "bidirectional"))
      (node (ref "U$8") (pin "2") (pinfunction "SBWTDIO_2") (pintype "bidirectional"))
    )
    (net (code "33") (name "Net-(U1-SENSE)") (class "Default")
      (node (ref "L1") (pin "2") (pinfunction "2_2") (pintype "passive"))
      (node (ref "R4") (pin "1") (pinfunction "1_1") (pintype "passive"))
      (node (ref "U1") (pin "10") (pinfunction "SENSE_10") (pintype "bidirectional"))
    )
    (net (code "34") (name "Net-(U1-SW)") (class "Default")
      (node (ref "C2") (pin "1") (pinfunction "1_1") (pintype "passive"))
      (node (ref "D2") (pin "C") (pinfunction "C_C") (pintype "passive"))
      (node (ref "L1") (pin "1") (pinfunction "1_1") (pintype "passive"))
      (node (ref "U1") (pin "12") (pinfunction "SW_12") (pintype "bidirectional"))
    )
    (net (code "35") (name "Net-(U1-VFB)") (class "Default")
      (node (ref "R3") (pin "1") (pinfunction "1_1") (pintype "passive"))
      (node (ref "R5") (pin "1") (pinfunction "1_1") (pintype "passive"))
      (node (ref "U1") (pin "7") (pinfunction "VFB_7") (pintype "bidirectional"))
    )
    (net (code "36") (name "Net-(U1-VIN)") (class "Default")
      (node (ref "C1") (pin "1") (pinfunction "1_1") (pintype "passive"))
      (node (ref "R1") (pin "2") (pinfunction "2_2") (pintype "passive"))
      (node (ref "R39") (pin "2") (pinfunction "2_2") (pintype "passive"))
      (node (ref "U1") (pin "1") (pinfunction "VIN_1") (pintype "bidirectional"))
    )
    (net (code "37") (name "Net-(U1-VIN_REG)") (class "Default")
      (node (ref "R1") (pin "1") (pinfunction "1_1") (pintype "passive"))
      (node (ref "R2") (pin "2") (pinfunction "2_2") (pintype "passive"))
      (node (ref "U1") (pin "2") (pinfunction "VIN_REG_2") (pintype "bidirectional"))
    )
    (net (code "38") (name "Net-(U1-~{SHDN})") (class "Default")
      (node (ref "R35") (pin "2") (pinfunction "2_2") (pintype "passive"))
      (node (ref "R36") (pin "2") (pinfunction "2_2") (pintype "passive"))
      (node (ref "U1") (pin "3") (pinfunction "~{SHDN}_3") (pintype "bidirectional"))
    )
    (net (code "39") (name "Net-(U2-SENSE)") (class "Default")
      (node (ref "L2") (pin "2") (pinfunction "2_2") (pintype "passive"))
      (node (ref "R8") (pin "1") (pinfunction "1_1") (pintype "passive"))
      (node (ref "U2") (pin "10") (pinfunction "SENSE_10") (pintype "bidirectional"))
    )
    (net (code "40") (name "Net-(U2-SW)") (class "Default")
      (node (ref "C10") (pin "1") (pinfunction "1_1") (pintype "passive"))
      (node (ref "D5") (pin "C") (pinfunction "C_C") (pintype "passive"))
      (node (ref "L2") (pin "1") (pinfunction "1_1") (pintype "passive"))
      (node (ref "U2") (pin "12") (pinfunction "SW_12") (pintype "bidirectional"))
    )
    (net (code "41") (name "Net-(U2-VFB)") (class "Default")
      (node (ref "R7") (pin "1") (pinfunction "1_1") (pintype "passive"))
      (node (ref "R9") (pin "1") (pinfunction "1_1") (pintype "passive"))
      (node (ref "U2") (pin "7") (pinfunction "VFB_7") (pintype "bidirectional"))
    )
    (net (code "42") (name "Net-(U2-VIN)") (class "Default")
      (node (ref "C4") (pin "1") (pinfunction "1_1") (pintype "passive"))
      (node (ref "R15") (pin "2") (pinfunction "2_2") (pintype "passive"))
      (node (ref "R38") (pin "2") (pinfunction "2_2") (pintype "passive"))
      (node (ref "U2") (pin "1") (pinfunction "VIN_1") (pintype "bidirectional"))
    )
    (net (code "43") (name "Net-(U2-VIN_REG)") (class "Default")
      (node (ref "R15") (pin "1") (pinfunction "1_1") (pintype "passive"))
      (node (ref "R21") (pin "2") (pinfunction "2_2") (pintype "passive"))
      (node (ref "U2") (pin "2") (pinfunction "VIN_REG_2") (pintype "bidirectional"))
    )
    (net (code "44") (name "Net-(U2-~{SHDN})") (class "Default")
      (node (ref "R33") (pin "2") (pinfunction "2_2") (pintype "passive"))
      (node (ref "R34") (pin "2") (pinfunction "2_2") (pintype "passive"))
      (node (ref "U2") (pin "3") (pinfunction "~{SHDN}_3") (pintype "bidirectional"))
    )
    (net (code "45") (name "Net-(U3-SENSE)") (class "Default")
      (node (ref "L3") (pin "2") (pinfunction "2_2") (pintype "passive"))
      (node (ref "R24") (pin "1") (pinfunction "1_1") (pintype "passive"))
      (node (ref "U3") (pin "10") (pinfunction "SENSE_10") (pintype "bidirectional"))
    )
    (net (code "46") (name "Net-(U3-SW)") (class "Default")
      (node (ref "C17") (pin "1") (pinfunction "1_1") (pintype "passive"))
      (node (ref "D8") (pin "C") (pinfunction "C_C") (pintype "passive"))
      (node (ref "L3") (pin "1") (pinfunction "1_1") (pintype "passive"))
      (node (ref "U3") (pin "12") (pinfunction "SW_12") (pintype "bidirectional"))
    )
    (net (code "47") (name "Net-(U3-VFB)") (class "Default")
      (node (ref "R23") (pin "1") (pinfunction "1_1") (pintype "passive"))
      (node (ref "R25") (pin "1") (pinfunction "1_1") (pintype "passive"))
      (node (ref "U3") (pin "7") (pinfunction "VFB_7") (pintype "bidirectional"))
    )
    (net (code "48") (name "Net-(U3-VIN)") (class "Default")
      (node (ref "C11") (pin "1") (pinfunction "1_1") (pintype "passive"))
      (node (ref "R31") (pin "2") (pinfunction "2_2") (pintype "passive"))
      (node (ref "R37") (pin "2") (pinfunction "2_2") (pintype "passive"))
      (node (ref "U3") (pin "1") (pinfunction "VIN_1") (pintype "bidirectional"))
    )
    (net (code "49") (name "Net-(U3-VIN_REG)") (class "Default")
      (node (ref "R31") (pin "1") (pinfunction "1_1") (pintype "passive"))
      (node (ref "R32") (pin "2") (pinfunction "2_2") (pintype "passive"))
      (node (ref "U3") (pin "2") (pinfunction "VIN_REG_2") (pintype "bidirectional"))
    )
    (net (code "50") (name "Net-(U3-~{SHDN})") (class "Default")
      (node (ref "R22") (pin "2") (pinfunction "2_2") (pintype "passive"))
      (node (ref "R6") (pin "2") (pinfunction "2_2") (pintype "passive"))
      (node (ref "U3") (pin "3") (pinfunction "~{SHDN}_3") (pintype "bidirectional"))
    )
    (net (code "51") (name "PNL1") (class "Default")
      (node (ref "JP1") (pin "1") (pinfunction "1_1") (pintype "passive"))
      (node (ref "R35") (pin "1") (pinfunction "1_1") (pintype "passive"))
      (node (ref "X1") (pin "1") (pinfunction "KL_1") (pintype "passive"))
    )
    (net (code "52") (name "PNL2") (class "Default")
      (node (ref "JP2") (pin "1") (pinfunction "1_1") (pintype "passive"))
      (node (ref "R33") (pin "1") (pinfunction "1_1") (pintype "passive"))
      (node (ref "X2") (pin "1") (pinfunction "KL_1") (pintype "passive"))
    )
    (net (code "53") (name "PNL3") (class "Default")
      (node (ref "JP3") (pin "1") (pinfunction "1_1") (pintype "passive"))
      (node (ref "R6") (pin "1") (pinfunction "1_1") (pintype "passive"))
      (node (ref "X3") (pin "1") (pinfunction "KL_1") (pintype "passive"))
    )
    (net (code "54") (name "SCL") (class "Default")
      (node (ref "J1") (pin "4") (pinfunction "4_4") (pintype "passive"))
      (node (ref "R12") (pin "2") (pinfunction "2_2") (pintype "passive"))
      (node (ref "R20") (pin "2") (pinfunction "2_2") (pintype "passive"))
      (node (ref "R28") (pin "2") (pinfunction "2_2") (pintype "passive"))
      (node (ref "U$1") (pin "5") (pinfunction "SCL_5") (pintype "input"))
      (node (ref "U$2") (pin "5") (pinfunction "SCL_5") (pintype "input"))
      (node (ref "U$3") (pin "5") (pinfunction "SCL_5") (pintype "input"))
      (node (ref "U$4") (pin "P$33") (pinfunction "P$33_P$33") (pintype "bidirectional"))
      (node (ref "U$5") (pin "P7.1_I2C-SCL-2") (pinfunction "P7.1_I2C-SCL-2_P7.1_I2C-SCL-2") (pintype "bidirectional"))
    )
    (net (code "55") (name "SDA") (class "Default")
      (node (ref "J1") (pin "3") (pinfunction "3_3") (pintype "passive"))
      (node (ref "R13") (pin "2") (pinfunction "2_2") (pintype "passive"))
      (node (ref "R19") (pin "2") (pinfunction "2_2") (pintype "passive"))
      (node (ref "R29") (pin "2") (pinfunction "2_2") (pintype "passive"))
      (node (ref "U$1") (pin "6") (pinfunction "SDA_6") (pintype "output"))
      (node (ref "U$2") (pin "6") (pinfunction "SDA_6") (pintype "output"))
      (node (ref "U$3") (pin "6") (pinfunction "SDA_6") (pintype "output"))
      (node (ref "U$4") (pin "P$37") (pinfunction "P$37_P$37") (pintype "bidirectional"))
      (node (ref "U$5") (pin "P7.0_I2C-SDA-2") (pinfunction "P7.0_I2C-SDA-2_P7.0_I2C-SDA-2") (pintype "bidirectional"))
    )
    (net (code "56") (name "SHDN1") (class "Default")
      (node (ref "J1") (pin "7") (pinfunction "7_7") (pintype "passive"))
      (node (ref "R36") (pin "1") (pinfunction "1_1") (pintype "passive"))
      (node (ref "U$5") (pin "P3.7_GPIO/PWM") (pinfunction "P3.7_GPIO/PWM_P3.7_GPIO/PWM") (pintype "bidirectional"))
    )
    (net (code "57") (name "SHDN2") (class "Default")
      (node (ref "J1") (pin "6") (pinfunction "6_6") (pintype "passive"))
      (node (ref "R34") (pin "1") (pinfunction "1_1") (pintype "passive"))
      (node (ref "U$5") (pin "P1.6_GPIO/PWM") (pinfunction "P1.6_GPIO/PWM_P1.6_GPIO/PWM") (pintype "bidirectional"))
    )
    (net (code "58") (name "SHDN3") (class "Default")
      (node (ref "J1") (pin "5") (pinfunction "5_5") (pintype "passive"))
      (node (ref "R22") (pin "1") (pinfunction "1_1") (pintype "passive"))
      (node (ref "U$5") (pin "P1.7_GPIO/PWM") (pinfunction "P1.7_GPIO/PWM_P1.7_GPIO/PWM") (pintype "bidirectional"))
    )
    (net (code "59") (name "SYNC1") (class "Default")
      (node (ref "U$4") (pin "P$45") (pinfunction "SYNC1_P$45") (pintype "bidirectional"))
      (node (ref "U$5") (pin "P7.2_SYNC1") (pinfunction "P7.2_SYNC1_P7.2_SYNC1") (pintype "bidirectional"))
    )
    (net (code "60") (name "SYNC2") (class "Default")
      (node (ref "U$4") (pin "P$49") (pinfunction "SYNC2_P$49") (pintype "bidirectional"))
      (node (ref "U$5") (pin "PJ.3_SYNC2") (pinfunction "PJ.3_SYNC2_PJ.3_SYNC2") (pintype "bidirectional"))
    )
    (net (code "61") (name "VBATT") (class "Default")
      (node (ref "JP4") (pin "2") (pinfunction "2_2") (pintype "passive"))
      (node (ref "JP5") (pin "2") (pinfunction "2_2") (pintype "passive"))
      (node (ref "JP6") (pin "2") (pinfunction "2_2") (pintype "passive"))
      (node (ref "U$4") (pin "P$18") (pinfunction "DISTRI_VBAT_P$18") (pintype "bidirectional"))
      (node (ref "U$4") (pin "P$20") (pinfunction "DISTRI_VBAT_P$20") (pintype "bidirectional"))
      (node (ref "U$4") (pin "P$21") (pinfunction "DISTRI_VBAT_P$21") (pintype "bidirectional"))
      (node (ref "U$4") (pin "P$23") (pinfunction "DISTRI_VBAT_P$23") (pintype "bidirectional"))
      (node (ref "U$4") (pin "P$26") (pinfunction "DISTRI_VBAT_P$26") (pintype "bidirectional"))
      (node (ref "U$4") (pin "P$28") (pinfunction "DISTRI_VBAT_P$28") (pintype "bidirectional"))
      (node (ref "U$4") (pin "P$29") (pinfunction "DISTRI_VBAT_P$29") (pintype "bidirectional"))
      (node (ref "U$4") (pin "P$31") (pinfunction "DISTRI_VBAT_P$31") (pintype "bidirectional"))
    )
    (net (code "62") (name "VS") (class "Default")
      (node (ref "C13") (pin "1") (pinfunction "1_1") (pintype "passive"))
      (node (ref "C15") (pin "1") (pinfunction "1_1") (pintype "passive"))
      (node (ref "C6") (pin "1") (pinfunction "1_1") (pintype "passive"))
      (node (ref "J1") (pin "1") (pinfunction "1_1") (pintype "passive"))
      (node (ref "R12") (pin "1") (pinfunction "1_1") (pintype "passive"))
      (node (ref "R13") (pin "1") (pinfunction "1_1") (pintype "passive"))
      (node (ref "R19") (pin "1") (pinfunction "1_1") (pintype "passive"))
      (node (ref "R20") (pin "1") (pinfunction "1_1") (pintype "passive"))
      (node (ref "R28") (pin "1") (pinfunction "1_1") (pintype "passive"))
      (node (ref "R29") (pin "1") (pinfunction "1_1") (pintype "passive"))
      (node (ref "R40") (pin "2") (pinfunction "2_2") (pintype "passive"))
      (node (ref "U$1") (pin "4") (pinfunction "VS_4") (pintype "power_in"))
      (node (ref "U$2") (pin "4") (pinfunction "VS_4") (pintype "power_in"))
      (node (ref "U$3") (pin "4") (pinfunction "VS_4") (pintype "power_in"))
      (node (ref "U$4") (pin "P$50") (pinfunction "5V_P$50") (pintype "bidirectional"))
      (node (ref "U$4") (pin "P$51") (pinfunction "5V_P$51") (pintype "bidirectional"))
    )
    (net (code "63") (name "VS_MSP") (class "Default")
      (node (ref "R40") (pin "1") (pinfunction "1_1") (pintype "passive"))
      (node (ref "U$5") (pin "5V") (pinfunction "5V_CAN_5V") (pintype "bidirectional"))
    )
    (net (code "64") (name "unconnected-(U$1-A0-Pad7)") (class "Default")
      (node (ref "U$1") (pin "7") (pinfunction "A0_7") (pintype "input"))
    )
    (net (code "65") (name "unconnected-(U$1-A1-Pad8)") (class "Default")
      (node (ref "U$1") (pin "8") (pinfunction "A1_8") (pintype "input"))
    )
    (net (code "66") (name "unconnected-(U$2-A0-Pad7)") (class "Default")
      (node (ref "U$2") (pin "7") (pinfunction "A0_7") (pintype "input"))
    )
    (net (code "67") (name "unconnected-(U$2-A1-Pad8)") (class "Default")
      (node (ref "U$2") (pin "8") (pinfunction "A1_8") (pintype "input"))
    )
    (net (code "68") (name "unconnected-(U$3-A0-Pad7)") (class "Default")
      (node (ref "U$3") (pin "7") (pinfunction "A0_7") (pintype "input"))
    )
    (net (code "69") (name "unconnected-(U$3-A1-Pad8)") (class "Default")
      (node (ref "U$3") (pin "8") (pinfunction "A1_8") (pintype "input"))
    )
    (net (code "70") (name "unconnected-(U$4-ADCS2_GND-PadP$82)") (class "Default")
      (node (ref "U$4") (pin "P$82") (pinfunction "ADCS2_GND_P$82") (pintype "bidirectional"))
    )
    (net (code "71") (name "unconnected-(U$4-ADCS2_GND-PadP$84)") (class "Default")
      (node (ref "U$4") (pin "P$84") (pinfunction "ADCS2_GND_P$84") (pintype "bidirectional"))
    )
    (net (code "72") (name "unconnected-(U$4-ADCS2_VBAT-PadP$81)") (class "Default")
      (node (ref "U$4") (pin "P$81") (pinfunction "ADCS2_VBAT_P$81") (pintype "bidirectional"))
    )
    (net (code "73") (name "unconnected-(U$4-ADCS2_VBAT-PadP$83)") (class "Default")
      (node (ref "U$4") (pin "P$83") (pinfunction "ADCS2_VBAT_P$83") (pintype "bidirectional"))
    )
    (net (code "74") (name "unconnected-(U$4-BDOT_GND-PadP$86)") (class "Default")
      (node (ref "U$4") (pin "P$86") (pinfunction "BDOT_GND_P$86") (pintype "bidirectional"))
    )
    (net (code "75") (name "unconnected-(U$4-BDOT_GND-PadP$88)") (class "Default")
      (node (ref "U$4") (pin "P$88") (pinfunction "BDOT_GND_P$88") (pintype "bidirectional"))
    )
    (net (code "76") (name "unconnected-(U$4-BDOT_I2C_SCL-PadP$90)") (class "Default")
      (node (ref "U$4") (pin "P$90") (pinfunction "BDOT_I2C_SCL_P$90") (pintype "bidirectional"))
    )
    (net (code "77") (name "unconnected-(U$4-BDOT_I2C_SDA-PadP$89)") (class "Default")
      (node (ref "U$4") (pin "P$89") (pinfunction "BDOT_I2C_SDA_P$89") (pintype "bidirectional"))
    )
    (net (code "78") (name "unconnected-(U$4-BDOT_VBAT-PadP$85)") (class "Default")
      (node (ref "U$4") (pin "P$85") (pinfunction "BDOT_VBAT_P$85") (pintype "bidirectional"))
    )
    (net (code "79") (name "unconnected-(U$4-BDOT_VBAT-PadP$87)") (class "Default")
      (node (ref "U$4") (pin "P$87") (pinfunction "BDOT_VBAT_P$87") (pintype "bidirectional"))
    )
    (net (code "80") (name "unconnected-(U$4-COM1_GND-PadP$102)") (class "Default")
      (node (ref "U$4") (pin "P$102") (pinfunction "COM1_GND_P$102") (pintype "bidirectional"))
    )
    (net (code "81") (name "unconnected-(U$4-COM1_GND-PadP$104)") (class "Default")
      (node (ref "U$4") (pin "P$104") (pinfunction "COM1_GND_P$104") (pintype "bidirectional"))
    )
    (net (code "82") (name "unconnected-(U$4-COM1_VBAT-PadP$101)") (class "Default")
      (node (ref "U$4") (pin "P$101") (pinfunction "COM1_VBAT_P$101") (pintype "bidirectional"))
    )
    (net (code "83") (name "unconnected-(U$4-COM1_VBAT-PadP$103)") (class "Default")
      (node (ref "U$4") (pin "P$103") (pinfunction "COM1_VBAT_P$103") (pintype "bidirectional"))
    )
    (net (code "84") (name "unconnected-(U$4-COM2_GND-PadP$98)") (class "Default")
      (node (ref "U$4") (pin "P$98") (pinfunction "COM2_GND_P$98") (pintype "bidirectional"))
    )
    (net (code "85") (name "unconnected-(U$4-COM2_GND-PadP$100)") (class "Default")
      (node (ref "U$4") (pin "P$100") (pinfunction "COM2_GND_P$100") (pintype "bidirectional"))
    )
    (net (code "86") (name "unconnected-(U$4-COM2_VBAT-PadP$97)") (class "Default")
      (node (ref "U$4") (pin "P$97") (pinfunction "COM2_VBAT_P$97") (pintype "bidirectional"))
    )
    (net (code "87") (name "unconnected-(U$4-COM2_VBAT-PadP$99)") (class "Default")
      (node (ref "U$4") (pin "P$99") (pinfunction "COM2_VBAT_P$99") (pintype "bidirectional"))
    )
    (net (code "88") (name "unconnected-(U$4-ESTIMAT_GND-PadP$78)") (class "Default")
      (node (ref "U$4") (pin "P$78") (pinfunction "ESTIMAT_GND_P$78") (pintype "bidirectional"))
    )
    (net (code "89") (name "unconnected-(U$4-ESTIMAT_GND-PadP$80)") (class "Default")
      (node (ref "U$4") (pin "P$80") (pinfunction "ESTIMAT_GND_P$80") (pintype "bidirectional"))
    )
    (net (code "90") (name "unconnected-(U$4-ESTIMAT_I2C_SCL-PadP$70)") (class "Default")
      (node (ref "U$4") (pin "P$70") (pinfunction "ESTIMAT_I2C_SCL_P$70") (pintype "bidirectional"))
    )
    (net (code "91") (name "unconnected-(U$4-ESTIMAT_I2C_SDA-PadP$69)") (class "Default")
      (node (ref "U$4") (pin "P$69") (pinfunction "ESTIMAT_I2C_SDA_P$69") (pintype "bidirectional"))
    )
    (net (code "92") (name "unconnected-(U$4-ESTIMAT_VBAT-PadP$77)") (class "Default")
      (node (ref "U$4") (pin "P$77") (pinfunction "ESTIMAT_VBAT_P$77") (pintype "bidirectional"))
    )
    (net (code "93") (name "unconnected-(U$4-ESTIMAT_VBAT-PadP$79)") (class "Default")
      (node (ref "U$4") (pin "P$79") (pinfunction "ESTIMAT_VBAT_P$79") (pintype "bidirectional"))
    )
    (net (code "94") (name "unconnected-(U$4-MAG1_PWM-PadP$73)") (class "Default")
      (node (ref "U$4") (pin "P$73") (pinfunction "MAG1_PWM_P$73") (pintype "bidirectional"))
    )
    (net (code "95") (name "unconnected-(U$4-MAG2_PWM-PadP$74)") (class "Default")
      (node (ref "U$4") (pin "P$74") (pinfunction "MAG2_PWM_P$74") (pintype "bidirectional"))
    )
    (net (code "96") (name "unconnected-(U$4-MAG3_PWM-PadP$75)") (class "Default")
      (node (ref "U$4") (pin "P$75") (pinfunction "MAG3_PWM_P$75") (pintype "bidirectional"))
    )
    (net (code "97") (name "unconnected-(U$4-MCU_GND-PadP$46)") (class "Default")
      (node (ref "U$4") (pin "P$46") (pinfunction "MCU_GND_P$46") (pintype "bidirectional"))
    )
    (net (code "98") (name "unconnected-(U$4-MCU_GND-PadP$47)") (class "Default")
      (node (ref "U$4") (pin "P$47") (pinfunction "MCU_GND_P$47") (pintype "bidirectional"))
    )
    (net (code "99") (name "unconnected-(U$4-MCU_GND-PadP$58)") (class "Default")
      (node (ref "U$4") (pin "P$58") (pinfunction "MCU_GND_P$58") (pintype "bidirectional"))
    )
    (net (code "100") (name "unconnected-(U$4-MCU_GND-PadP$59)") (class "Default")
      (node (ref "U$4") (pin "P$59") (pinfunction "MCU_GND_P$59") (pintype "bidirectional"))
    )
    (net (code "101") (name "unconnected-(U$4-PPT_GND-PadP$1)") (class "Default")
      (node (ref "U$4") (pin "P$1") (pinfunction "PPT_GND_P$1") (pintype "bidirectional"))
    )
    (net (code "102") (name "unconnected-(U$4-PPT_GND-PadP$3)") (class "Default")
      (node (ref "U$4") (pin "P$3") (pinfunction "PPT_GND_P$3") (pintype "bidirectional"))
    )
    (net (code "103") (name "unconnected-(U$4-PPT_GND-PadP$6)") (class "Default")
      (node (ref "U$4") (pin "P$6") (pinfunction "PPT_GND_P$6") (pintype "bidirectional"))
    )
    (net (code "104") (name "unconnected-(U$4-PPT_GND-PadP$8)") (class "Default")
      (node (ref "U$4") (pin "P$8") (pinfunction "PPT_GND_P$8") (pintype "bidirectional"))
    )
    (net (code "105") (name "unconnected-(U$4-PPT_GND-PadP$9)") (class "Default")
      (node (ref "U$4") (pin "P$9") (pinfunction "PPT_GND_P$9") (pintype "bidirectional"))
    )
    (net (code "106") (name "unconnected-(U$4-PPT_GND-PadP$11)") (class "Default")
      (node (ref "U$4") (pin "P$11") (pinfunction "PPT_GND_P$11") (pintype "bidirectional"))
    )
    (net (code "107") (name "unconnected-(U$4-PPT_GND-PadP$14)") (class "Default")
      (node (ref "U$4") (pin "P$14") (pinfunction "PPT_GND_P$14") (pintype "bidirectional"))
    )
    (net (code "108") (name "unconnected-(U$4-PPT_GND-PadP$16)") (class "Default")
      (node (ref "U$4") (pin "P$16") (pinfunction "PPT_GND_P$16") (pintype "bidirectional"))
    )
    (net (code "109") (name "unconnected-(U$4-PPT_VBAT-PadP$2)") (class "Default")
      (node (ref "U$4") (pin "P$2") (pinfunction "PPT_VBAT_P$2") (pintype "bidirectional"))
    )
    (net (code "110") (name "unconnected-(U$4-PPT_VBAT-PadP$4)") (class "Default")
      (node (ref "U$4") (pin "P$4") (pinfunction "PPT_VBAT_P$4") (pintype "bidirectional"))
    )
    (net (code "111") (name "unconnected-(U$4-PPT_VBAT-PadP$5)") (class "Default")
      (node (ref "U$4") (pin "P$5") (pinfunction "PPT_VBAT_P$5") (pintype "bidirectional"))
    )
    (net (code "112") (name "unconnected-(U$4-PPT_VBAT-PadP$7)") (class "Default")
      (node (ref "U$4") (pin "P$7") (pinfunction "PPT_VBAT_P$7") (pintype "bidirectional"))
    )
    (net (code "113") (name "unconnected-(U$4-PPT_VBAT-PadP$10)") (class "Default")
      (node (ref "U$4") (pin "P$10") (pinfunction "PPT_VBAT_P$10") (pintype "bidirectional"))
    )
    (net (code "114") (name "unconnected-(U$4-PPT_VBAT-PadP$12)") (class "Default")
      (node (ref "U$4") (pin "P$12") (pinfunction "PPT_VBAT_P$12") (pintype "bidirectional"))
    )
    (net (code "115") (name "unconnected-(U$4-PPT_VBAT-PadP$13)") (class "Default")
      (node (ref "U$4") (pin "P$13") (pinfunction "PPT_VBAT_P$13") (pintype "bidirectional"))
    )
    (net (code "116") (name "unconnected-(U$4-PPT_VBAT-PadP$15)") (class "Default")
      (node (ref "U$4") (pin "P$15") (pinfunction "PPT_VBAT_P$15") (pintype "bidirectional"))
    )
    (net (code "117") (name "unconnected-(U$4-PadP$34)") (class "Default")
      (node (ref "U$4") (pin "P$34") (pinfunction "P$34_P$34") (pintype "bidirectional"))
    )
    (net (code "118") (name "unconnected-(U$4-PadP$35)") (class "Default")
      (node (ref "U$4") (pin "P$35") (pinfunction "P$35_P$35") (pintype "bidirectional"))
    )
    (net (code "119") (name "unconnected-(U$4-PadP$36)") (class "Default")
      (node (ref "U$4") (pin "P$36") (pinfunction "P$36_P$36") (pintype "bidirectional"))
    )
    (net (code "120") (name "unconnected-(U$4-PadP$38)") (class "Default")
      (node (ref "U$4") (pin "P$38") (pinfunction "P$38_P$38") (pintype "bidirectional"))
    )
    (net (code "121") (name "unconnected-(U$4-PadP$39)") (class "Default")
      (node (ref "U$4") (pin "P$39") (pinfunction "P$39_P$39") (pintype "bidirectional"))
    )
    (net (code "122") (name "unconnected-(U$4-PadP$40)") (class "Default")
      (node (ref "U$4") (pin "P$40") (pinfunction "P$40_P$40") (pintype "bidirectional"))
    )
    (net (code "123") (name "unconnected-(U$4-PadP$41)") (class "Default")
      (node (ref "U$4") (pin "P$41") (pinfunction "P$41_P$41") (pintype "bidirectional"))
    )
    (net (code "124") (name "unconnected-(U$4-PadP$42)") (class "Default")
      (node (ref "U$4") (pin "P$42") (pinfunction "P$42_P$42") (pintype "bidirectional"))
    )
    (net (code "125") (name "unconnected-(U$4-PadP$43)") (class "Default")
      (node (ref "U$4") (pin "P$43") (pinfunction "P$43_P$43") (pintype "bidirectional"))
    )
    (net (code "126") (name "unconnected-(U$4-PadP$44)") (class "Default")
      (node (ref "U$4") (pin "P$44") (pinfunction "P$44_P$44") (pintype "bidirectional"))
    )
    (net (code "127") (name "unconnected-(U$4-PadP$48)") (class "Default")
      (node (ref "U$4") (pin "P$48") (pinfunction "P$48_P$48") (pintype "bidirectional"))
    )
    (net (code "128") (name "unconnected-(U$4-PadP$52)") (class "Default")
      (node (ref "U$4") (pin "P$52") (pinfunction "P$52_P$52") (pintype "bidirectional"))
    )
    (net (code "129") (name "unconnected-(U$4-PadP$56)") (class "Default")
      (node (ref "U$4") (pin "P$56") (pinfunction "P$56_P$56") (pintype "bidirectional"))
    )
    (net (code "130") (name "unconnected-(U$4-PadP$60)") (class "Default")
      (node (ref "U$4") (pin "P$60") (pinfunction "P$60_P$60") (pintype "bidirectional"))
    )
    (net (code "131") (name "unconnected-(U$4-PadP$61)") (class "Default")
      (node (ref "U$4") (pin "P$61") (pinfunction "P$61_P$61") (pintype "bidirectional"))
    )
    (net (code "132") (name "unconnected-(U$4-PadP$62)") (class "Default")
      (node (ref "U$4") (pin "P$62") (pinfunction "P$62_P$62") (pintype "bidirectional"))
    )
    (net (code "133") (name "unconnected-(U$4-PadP$63)") (class "Default")
      (node (ref "U$4") (pin "P$63") (pinfunction "P$63_P$63") (pintype "bidirectional"))
    )
    (net (code "134") (name "unconnected-(U$4-PadP$64)") (class "Default")
      (node (ref "U$4") (pin "P$64") (pinfunction "P$64_P$64") (pintype "bidirectional"))
    )
    (net (code "135") (name "unconnected-(U$4-PadP$65)") (class "Default")
      (node (ref "U$4") (pin "P$65") (pinfunction "P$65_P$65") (pintype "bidirectional"))
    )
    (net (code "136") (name "unconnected-(U$4-PadP$66)") (class "Default")
      (node (ref "U$4") (pin "P$66") (pinfunction "P$66_P$66") (pintype "bidirectional"))
    )
    (net (code "137") (name "unconnected-(U$4-PadP$67)") (class "Default")
      (node (ref "U$4") (pin "P$67") (pinfunction "P$67_P$67") (pintype "bidirectional"))
    )
    (net (code "138") (name "unconnected-(U$4-PadP$68)") (class "Default")
      (node (ref "U$4") (pin "P$68") (pinfunction "P$68_P$68") (pintype "bidirectional"))
    )
    (net (code "139") (name "unconnected-(U$4-PadP$71)") (class "Default")
      (node (ref "U$4") (pin "P$71") (pinfunction "P$71_P$71") (pintype "bidirectional"))
    )
    (net (code "140") (name "unconnected-(U$4-PadP$72)") (class "Default")
      (node (ref "U$4") (pin "P$72") (pinfunction "P$72_P$72") (pintype "bidirectional"))
    )
    (net (code "141") (name "unconnected-(U$4-PadP$76)") (class "Default")
      (node (ref "U$4") (pin "P$76") (pinfunction "P$76_P$76") (pintype "bidirectional"))
    )
    (net (code "142") (name "unconnected-(U$4-PadP$91)") (class "Default")
      (node (ref "U$4") (pin "P$91") (pinfunction "P$91_P$91") (pintype "bidirectional"))
    )
    (net (code "143") (name "unconnected-(U$4-PadP$92)") (class "Default")
      (node (ref "U$4") (pin "P$92") (pinfunction "P$92_P$92") (pintype "bidirectional"))
    )
    (net (code "144") (name "unconnected-(U$4-PadP$95)") (class "Default")
      (node (ref "U$4") (pin "P$95") (pinfunction "P$95_P$95") (pintype "bidirectional"))
    )
    (net (code "145") (name "unconnected-(U$4-PadP$96)") (class "Default")
      (node (ref "U$4") (pin "P$96") (pinfunction "P$96_P$96") (pintype "bidirectional"))
    )
    (net (code "146") (name "unconnected-(U$4-RAHS_GND-PadP$94)") (class "Default")
      (node (ref "U$4") (pin "P$94") (pinfunction "RAHS_GND_P$94") (pintype "bidirectional"))
    )
    (net (code "147") (name "unconnected-(U$4-RAHS_VBAT-PadP$93)") (class "Default")
      (node (ref "U$4") (pin "P$93") (pinfunction "RAHS_VBAT_P$93") (pintype "bidirectional"))
    )
    (net (code "148") (name "unconnected-(U$5-P2.3_SPI-CS2-PadP2.4_SPI-CS2)") (class "Default")
      (node (ref "U$5") (pin "P2.4_SPI-CS2") (pinfunction "P2.3_SPI-CS2_P2.4_SPI-CS2") (pintype "bidirectional"))
    )
    (net (code "149") (name "unconnected-(U$5-PadP1.0_A0)") (class "Default")
      (node (ref "U$5") (pin "P1.0_A0") (pinfunction "P1.0_A0_P1.0_A0") (pintype "bidirectional"))
    )
    (net (code "150") (name "unconnected-(U$5-PadP1.1_A1)") (class "Default")
      (node (ref "U$5") (pin "P1.1_A1") (pinfunction "P1.1_A1_P1.1_A1") (pintype "bidirectional"))
    )
    (net (code "151") (name "unconnected-(U$5-PadP1.2_A2)") (class "Default")
      (node (ref "U$5") (pin "P1.2_A2") (pinfunction "P1.2_A2_P1.2_A2") (pintype "bidirectional"))
    )
    (net (code "152") (name "unconnected-(U$5-PadP1.3_A3)") (class "Default")
      (node (ref "U$5") (pin "P1.3_A3") (pinfunction "P1.3_A3_P1.3_A3") (pintype "bidirectional"))
    )
    (net (code "153") (name "unconnected-(U$5-PadP1.4_A4)") (class "Default")
      (node (ref "U$5") (pin "P1.4_A4") (pinfunction "P1.4_A4_P1.4_A4") (pintype "bidirectional"))
    )
    (net (code "154") (name "unconnected-(U$5-PadP1.5_A5)") (class "Default")
      (node (ref "U$5") (pin "P1.5_A5") (pinfunction "P1.5_A5_P1.5_A5") (pintype "bidirectional"))
    )
    (net (code "155") (name "unconnected-(U$5-PadP2.2_GPIO{slash}PWM)") (class "Default")
      (node (ref "U$5") (pin "P2.2_GPIO/PWM") (pinfunction "P2.2_GPIO/PWM_P2.2_GPIO/PWM") (pintype "bidirectional"))
    )
    (net (code "156") (name "unconnected-(U$5-PadP2.5_GPIO)") (class "Default")
      (node (ref "U$5") (pin "P2.5_GPIO") (pinfunction "P2.5_GPIO_P2.5_GPIO") (pintype "bidirectional"))
    )
    (net (code "157") (name "unconnected-(U$5-PadP2.6_GPIO{slash}PWM)") (class "Default")
      (node (ref "U$5") (pin "P2.6_GPIO/PWM") (pinfunction "P2.6_GPIO/PWM_P2.6_GPIO/PWM") (pintype "bidirectional"))
    )
    (net (code "158") (name "unconnected-(U$5-PadP2.7_SPI-CS3)") (class "Default")
      (node (ref "U$5") (pin "P2.7_SPI-CS3") (pinfunction "P2.7_SPI-CS3_P2.7_SPI-CS3") (pintype "bidirectional"))
    )
    (net (code "159") (name "unconnected-(U$5-PadP3.0_A12)") (class "Default")
      (node (ref "U$5") (pin "P3.0_A12") (pinfunction "P3.0_A12_P3.0_A12") (pintype "bidirectional"))
    )
    (net (code "160") (name "unconnected-(U$5-PadP3.1_A13)") (class "Default")
      (node (ref "U$5") (pin "P3.1_A13") (pinfunction "P3.1_A13_P3.1_A13") (pintype "bidirectional"))
    )
    (net (code "161") (name "unconnected-(U$5-PadP3.2_A14)") (class "Default")
      (node (ref "U$5") (pin "P3.2_A14") (pinfunction "P3.2_A14_P3.2_A14") (pintype "bidirectional"))
    )
    (net (code "162") (name "unconnected-(U$5-PadP3.3_A15)") (class "Default")
      (node (ref "U$5") (pin "P3.3_A15") (pinfunction "P3.3_A15_P3.3_A15") (pintype "bidirectional"))
    )
    (net (code "163") (name "unconnected-(U$5-PadP3.6_GPIO{slash}PWM)") (class "Default")
      (node (ref "U$5") (pin "P3.6_GPIO/PWM") (pinfunction "P3.6_GPIO/PWM_P3.6_GPIO/PWM") (pintype "bidirectional"))
    )
    (net (code "164") (name "unconnected-(U$5-PadP4.0_GPIO)") (class "Default")
      (node (ref "U$5") (pin "P4.0_GPIO") (pinfunction "P4.0_GPIO_P4.0_GPIO") (pintype "bidirectional"))
    )
    (net (code "165") (name "unconnected-(U$5-PadP4.1_GPIO)") (class "Default")
      (node (ref "U$5") (pin "P4.1_GPIO") (pinfunction "P4.1_GPIO_P4.1_GPIO") (pintype "bidirectional"))
    )
    (net (code "166") (name "unconnected-(U$5-PadP4.2_GPIO)") (class "Default")
      (node (ref "U$5") (pin "P4.2_GPIO") (pinfunction "P4.2_GPIO_P4.2_GPIO") (pintype "bidirectional"))
    )
    (net (code "167") (name "unconnected-(U$5-PadP4.3_GPIO)") (class "Default")
      (node (ref "U$5") (pin "P4.3_GPIO") (pinfunction "P4.3_GPIO_P4.3_GPIO") (pintype "bidirectional"))
    )
    (net (code "168") (name "unconnected-(U$5-PadP5.0_I2C-SDA-1)") (class "Default")
      (node (ref "U$5") (pin "P5.0_I2C-SDA-1") (pinfunction "P5.0_I2C-SDA-1_P5.0_I2C-SDA-1") (pintype "bidirectional"))
    )
    (net (code "169") (name "unconnected-(U$5-PadP5.1_I2C-SCL-1)") (class "Default")
      (node (ref "U$5") (pin "P5.1_I2C-SCL-1") (pinfunction "P5.1_I2C-SCL-1_P5.1_I2C-SCL-1") (pintype "bidirectional"))
    )
    (net (code "170") (name "unconnected-(U$5-PadP5.4_SPI-MOSI)") (class "Default")
      (node (ref "U$5") (pin "P5.4_SPI-MOSI") (pinfunction "P5.4_SPI-MOSI_P5.4_SPI-MOSI") (pintype "bidirectional"))
    )
    (net (code "171") (name "unconnected-(U$5-PadP5.5_SPI-MISO)") (class "Default")
      (node (ref "U$5") (pin "P5.5_SPI-MISO") (pinfunction "P5.5_SPI-MISO_P5.5_SPI-MISO") (pintype "bidirectional"))
    )
    (net (code "172") (name "unconnected-(U$5-PadP5.6_SPI-CLK)") (class "Default")
      (node (ref "U$5") (pin "P5.6_SPI-CLK") (pinfunction "P5.6_SPI-CLK_P5.6_SPI-CLK") (pintype "bidirectional"))
    )
    (net (code "173") (name "unconnected-(U$5-PadP7.3_GPIO)") (class "Default")
      (node (ref "U$5") (pin "P7.3_GPIO") (pinfunction "P7.3_GPIO_P7.3_GPIO") (pintype "bidirectional"))
    )
    (net (code "174") (name "unconnected-(U$5-PadP7.4_GPIO)") (class "Default")
      (node (ref "U$5") (pin "P7.4_GPIO") (pinfunction "P7.4_GPIO_P7.4_GPIO") (pintype "bidirectional"))
    )
    (net (code "175") (name "unconnected-(U1-NTC-Pad8)") (class "Default")
      (node (ref "U1") (pin "8") (pinfunction "NTC_8") (pintype "bidirectional"))
    )
    (net (code "176") (name "unconnected-(U1-~{CHRG}-Pad4)") (class "Default")
      (node (ref "U1") (pin "4") (pinfunction "~{CHRG}_4") (pintype "bidirectional"))
    )
    (net (code "177") (name "unconnected-(U1-~{FAULT}-Pad5)") (class "Default")
      (node (ref "U1") (pin "5") (pinfunction "~{FAULT}_5") (pintype "bidirectional"))
    )
    (net (code "178") (name "unconnected-(U2-NTC-Pad8)") (class "Default")
      (node (ref "U2") (pin "8") (pinfunction "NTC_8") (pintype "bidirectional"))
    )
    (net (code "179") (name "unconnected-(U2-~{CHRG}-Pad4)") (class "Default")
      (node (ref "U2") (pin "4") (pinfunction "~{CHRG}_4") (pintype "bidirectional"))
    )
    (net (code "180") (name "unconnected-(U2-~{FAULT}-Pad5)") (class "Default")
      (node (ref "U2") (pin "5") (pinfunction "~{FAULT}_5") (pintype "bidirectional"))
    )
    (net (code "181") (name "unconnected-(U3-NTC-Pad8)") (class "Default")
      (node (ref "U3") (pin "8") (pinfunction "NTC_8") (pintype "bidirectional"))
    )
    (net (code "182") (name "unconnected-(U3-~{CHRG}-Pad4)") (class "Default")
      (node (ref "U3") (pin "4") (pinfunction "~{CHRG}_4") (pintype "bidirectional"))
    )
    (net (code "183") (name "unconnected-(U3-~{FAULT}-Pad5)") (class "Default")
      (node (ref "U3") (pin "5") (pinfunction "~{FAULT}_5") (pintype "bidirectional"))
    )
  )
)
